# ADL5330.net
KiCad netlist of a schematic drawn in Altium Designer
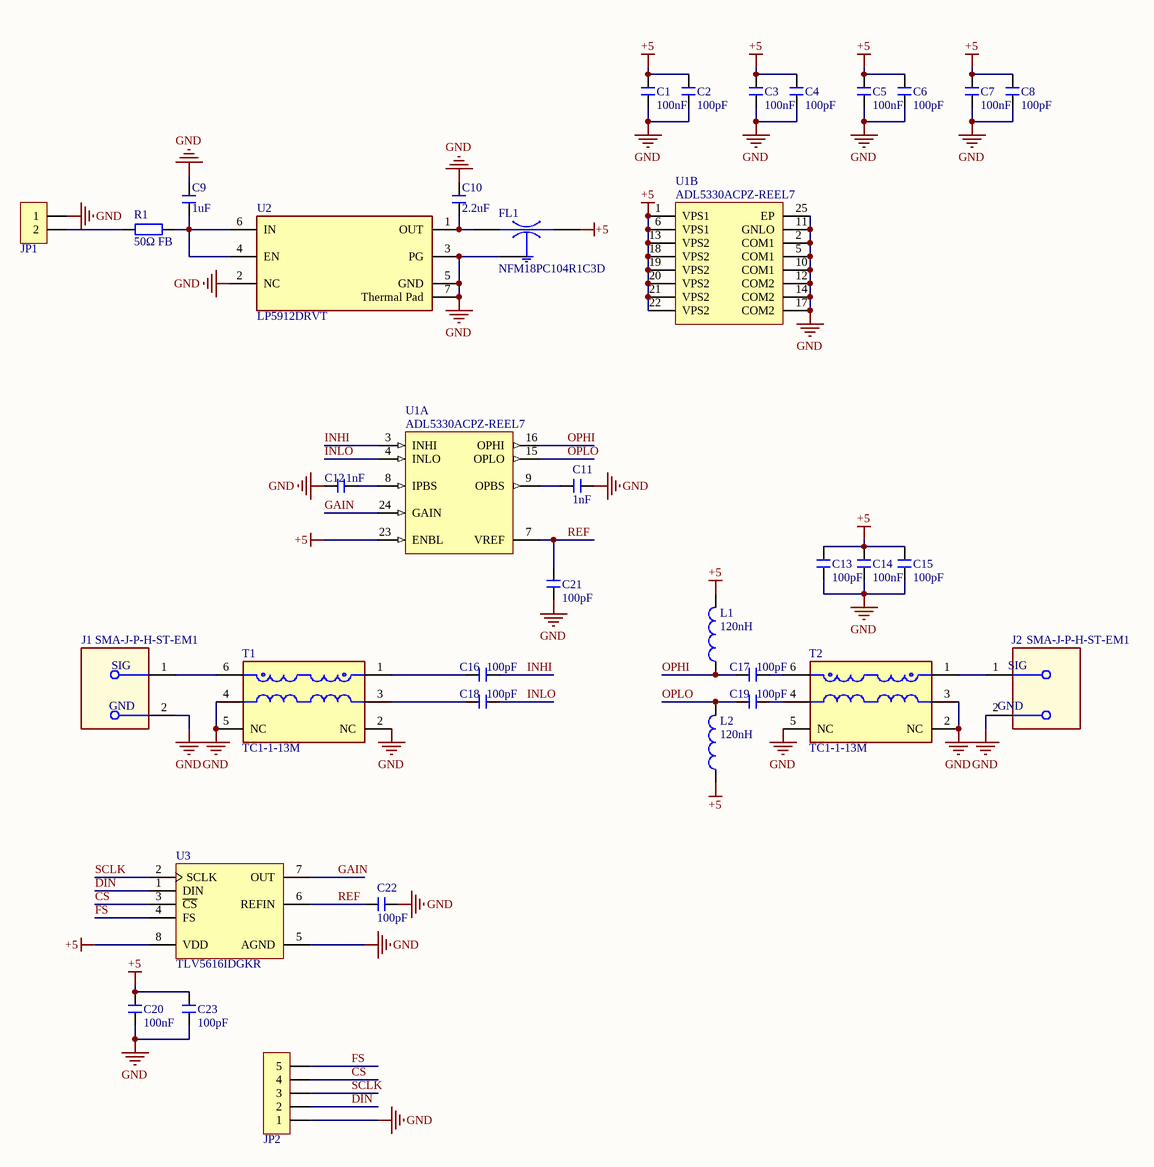
[diagram p0: ADL5330.SchDoc]

(export (version "E")
  (design (tool "Eeschema 10.0.6"))
  (components
    (comp (ref "C1")
      (value "100nF")
      (footprint "C 0402_L")
      (description "贴片电容")
      (libsource (lib "01 - 电容-电阻-电感") (part "C"))
    )
    (comp (ref "C2")
      (value "100pF")
      (footprint "C 0402_L")
      (description "贴片电容")
      (libsource (lib "01 - 电容-电阻-电感") (part "C"))
    )
    (comp (ref "C3")
      (value "100nF")
      (footprint "C 0402_L")
      (description "贴片电容")
      (libsource (lib "01 - 电容-电阻-电感") (part "C"))
    )
    (comp (ref "C4")
      (value "100pF")
      (footprint "C 0402_L")
      (description "贴片电容")
      (libsource (lib "01 - 电容-电阻-电感") (part "C"))
    )
    (comp (ref "C5")
      (value "100nF")
      (footprint "C 0402_L")
      (description "贴片电容")
      (libsource (lib "01 - 电容-电阻-电感") (part "C"))
    )
    (comp (ref "C6")
      (value "100pF")
      (footprint "C 0402_L")
      (description "贴片电容")
      (libsource (lib "01 - 电容-电阻-电感") (part "C"))
    )
    (comp (ref "C7")
      (value "100nF")
      (footprint "C 0402_L")
      (description "贴片电容")
      (libsource (lib "01 - 电容-电阻-电感") (part "C"))
    )
    (comp (ref "C8")
      (value "100pF")
      (footprint "C 0402_L")
      (description "贴片电容")
      (libsource (lib "01 - 电容-电阻-电感") (part "C"))
    )
    (comp (ref "C9")
      (value "1uF")
      (footprint "C 0603_L")
      (description "贴片电容")
      (libsource (lib "01 - 电容-电阻-电感") (part "C"))
    )
    (comp (ref "C10")
      (value "2.2uF")
      (footprint "C 0603_L")
      (description "贴片电容")
      (libsource (lib "01 - 电容-电阻-电感") (part "C"))
    )
    (comp (ref "C11")
      (value "1nF")
      (footprint "C 0402_L")
      (description "贴片电容")
      (libsource (lib "01 - 电容-电阻-电感") (part "C"))
    )
    (comp (ref "C12")
      (value "1nF")
      (footprint "C 0402_L")
      (description "贴片电容")
      (libsource (lib "01 - 电容-电阻-电感") (part "C"))
    )
    (comp (ref "C13")
      (value "100pF")
      (footprint "C 0402_L")
      (description "贴片电容")
      (libsource (lib "01 - 电容-电阻-电感") (part "C"))
    )
    (comp (ref "C14")
      (value "100nF")
      (footprint "C 0402_L")
      (description "贴片电容")
      (libsource (lib "01 - 电容-电阻-电感") (part "C"))
    )
    (comp (ref "C15")
      (value "100pF")
      (footprint "C 0402_L")
      (description "贴片电容")
      (libsource (lib "01 - 电容-电阻-电感") (part "C"))
    )
    (comp (ref "C16")
      (value "100pF")
      (footprint "C 0402_L")
      (description "贴片电容")
      (libsource (lib "01 - 电容-电阻-电感") (part "C"))
    )
    (comp (ref "C17")
      (value "100pF")
      (footprint "C 0402_L")
      (description "贴片电容")
      (libsource (lib "01 - 电容-电阻-电感") (part "C"))
    )
    (comp (ref "C18")
      (value "100pF")
      (footprint "C 0402_L")
      (description "贴片电容")
      (libsource (lib "01 - 电容-电阻-电感") (part "C"))
    )
    (comp (ref "C19")
      (value "100pF")
      (footprint "C 0402_L")
      (description "贴片电容")
      (libsource (lib "01 - 电容-电阻-电感") (part "C"))
    )
    (comp (ref "C20")
      (value "100nF")
      (footprint "C 0402_L")
      (description "贴片电容")
      (libsource (lib "01 - 电容-电阻-电感") (part "C"))
    )
    (comp (ref "C21")
      (value "100pF")
      (footprint "C 0402_L")
      (description "贴片电容")
      (libsource (lib "01 - 电容-电阻-电感") (part "C"))
    )
    (comp (ref "C22")
      (value "100pF")
      (footprint "C 0402_L")
      (description "贴片电容")
      (libsource (lib "01 - 电容-电阻-电感") (part "C"))
    )
    (comp (ref "C23")
      (value "100pF")
      (footprint "C 0402_L")
      (description "贴片电容")
      (libsource (lib "01 - 电容-电阻-电感") (part "C"))
    )
    (comp (ref "FL1")
      (value "NFM18PC104R1C3D")
      (footprint "FIL_NFM18PC104R1C3D")
      (description "SMD Capacitor with Capacitance: 0.10uF Tol. 20%. Rated Voltage: 16Vdc")
      (fields (field (name "MF") "Murata") (field (name "DIGI-KEY_PART_NUMBER") "490-6969-1-ND"))
      (libsource (lib "NFM18PC104R1C3D") (part "NFM18PC104R1C3D"))
    )
    (comp (ref "J1")
      (value "SMA-J-P-H-ST-EM1")
      (footprint "FP-SMA-J-P-H-ST-EM1-MFG")
      (description "CONN SMA JACK STR 50OHM EDGE MNT")
      (libsource (lib "") (part "CMP-02754-000006-1_1"))
    )
    (comp (ref "J2")
      (value "SMA-J-P-H-ST-EM1")
      (footprint "FP-SMA-J-P-H-ST-EM1-MFG")
      (description "CONN SMA JACK STR 50OHM EDGE MNT")
      (libsource (lib "卧式SMA") (part "CMP-02754-000006-1"))
    )
    (comp (ref "JP1")
      (value "HDR-1X2")
      (footprint "KF2510-LI-2P")
      (description "2P接插件")
      (libsource (lib "18 - 接插件-脚距2.54mm (100mil) ") (part "Header 2"))
    )
    (comp (ref "JP2")
      (value "HDR-1X5")
      (footprint "HDR2.54-LI-5P")
      (description "5P接插件")
      (libsource (lib "18 - 接插件-脚距2.54mm (100mil) ") (part "Header 5"))
    )
    (comp (ref "L1")
      (value "120nH")
      (footprint "L 0603")
      (description "小功率贴片电感")
      (libsource (lib "01 - 电容-电阻-电感") (part "L"))
    )
    (comp (ref "L2")
      (value "120nH")
      (footprint "L 0603")
      (description "小功率贴片电感")
      (libsource (lib "01 - 电容-电阻-电感") (part "L"))
    )
    (comp (ref "R1")
      (value "50Ω FB")
      (footprint "R 1206_L")
      (description "贴片电阻")
      (libsource (lib "01 - 电容-电阻-电感") (part "R"))
    )
    (comp (ref "T1")
      (value "TC1-1-13M")
      (footprint "FP-TC1-1-13M+-MFG")
      (description "RF Transformer 1: 1 5 Terminal SMD")
      (libsource (lib "TC1-1-13M+") (part "TC1-1-13M"))
    )
    (comp (ref "T2")
      (value "TC1-1-13M")
      (footprint "FP-TC1-1-13M+-MFG")
      (description "RF Transformer 1: 1 5 Terminal SMD")
      (libsource (lib "TC1-1-13M+") (part "TC1-1-13M"))
    )
    (comp (ref "U1")
      (value "ADL5330ACPZ-REEL7")
      (footprint "ADI-CP-24-2_L")
      (description "10 MHz to 3 GHz VGA with 60 dB Gain Control Range, 3GHz, CP-24-2, 1500 Reel, Pb-Free")
      (libsource (lib "ADL5330ACPZ") (part "ADL5330ACPZ"))
    )
    (comp (ref "U2")
      (value "LP5912DRVT")
      (footprint "FP-DRV0006A-MFG")
      (description "IC REG LINEAR 500MA 6SON")
      (libsource (lib "LP5912") (part "LP5912DRVT"))
    )
    (comp (ref "U3")
      (value "TLV5616IDGKR")
      (footprint "TI-DGK8_L")
      (fields (field (name "MANUFACTURER") "Texas Instruments"))
      (libsource (lib "TLV5616IDGKR") (part "CMP-0004-00436-1"))
    )
  )
  (nets
    (net (code "1") (name "+5") (class "Default")
      (node (ref "C1") (pin "2") (pinfunction "2_2") (pintype "passive"))
      (node (ref "C13") (pin "2") (pinfunction "2_2") (pintype "passive"))
      (node (ref "C14") (pin "2") (pinfunction "2_2") (pintype "passive"))
      (node (ref "C15") (pin "2") (pinfunction "2_2") (pintype "passive"))
      (node (ref "C2") (pin "2") (pinfunction "2_2") (pintype "passive"))
      (node (ref "C20") (pin "2") (pinfunction "2_2") (pintype "passive"))
      (node (ref "C23") (pin "1") (pinfunction "1_1") (pintype "passive"))
      (node (ref "C3") (pin "2") (pinfunction "2_2") (pintype "passive"))
      (node (ref "C4") (pin "2") (pinfunction "2_2") (pintype "passive"))
      (node (ref "C5") (pin "2") (pinfunction "2_2") (pintype "passive"))
      (node (ref "C6") (pin "2") (pinfunction "2_2") (pintype "passive"))
      (node (ref "C7") (pin "2") (pinfunction "2_2") (pintype "passive"))
      (node (ref "C8") (pin "2") (pinfunction "2_2") (pintype "passive"))
      (node (ref "FL1") (pin "3") (pinfunction "OUT_3") (pintype "passive"))
      (node (ref "L1") (pin "2") (pinfunction "2_2") (pintype "passive"))
      (node (ref "L2") (pin "1") (pinfunction "1_1") (pintype "passive"))
      (node (ref "U1") (pin "1") (pinfunction "VPS1_1") (pintype "power_in"))
      (node (ref "U1") (pin "13") (pinfunction "VPS2_13") (pintype "power_in"))
      (node (ref "U1") (pin "18") (pinfunction "VPS2_18") (pintype "power_in"))
      (node (ref "U1") (pin "19") (pinfunction "VPS2_19") (pintype "power_in"))
      (node (ref "U1") (pin "20") (pinfunction "VPS2_20") (pintype "power_in"))
      (node (ref "U1") (pin "21") (pinfunction "VPS2_21") (pintype "power_in"))
      (node (ref "U1") (pin "22") (pinfunction "VPS2_22") (pintype "power_in"))
      (node (ref "U1") (pin "23") (pinfunction "ENBL_23") (pintype "input"))
      (node (ref "U1") (pin "6") (pinfunction "VPS1_6") (pintype "power_in"))
      (node (ref "U3") (pin "8") (pinfunction "VDD_8") (pintype "power_in"))
    )
    (net (code "2") (name "/DIN") (class "Default")
      (node (ref "JP2") (pin "2") (pinfunction "2_2") (pintype "passive"))
      (node (ref "U3") (pin "1") (pinfunction "DIN_1") (pintype "passive"))
    )
    (net (code "3") (name "/FS") (class "Default")
      (node (ref "JP2") (pin "5") (pinfunction "5_5") (pintype "passive"))
      (node (ref "U3") (pin "4") (pinfunction "FS_4") (pintype "passive"))
    )
    (net (code "4") (name "/GAIN") (class "Default")
      (node (ref "U1") (pin "24") (pinfunction "GAIN_24") (pintype "input"))
      (node (ref "U3") (pin "7") (pinfunction "OUT_7") (pintype "passive"))
    )
    (net (code "5") (name "/INHI") (class "Default")
      (node (ref "C16") (pin "2") (pinfunction "2_2") (pintype "passive"))
      (node (ref "U1") (pin "3") (pinfunction "INHI_3") (pintype "input"))
    )
    (net (code "6") (name "/INLO") (class "Default")
      (node (ref "C18") (pin "2") (pinfunction "2_2") (pintype "passive"))
      (node (ref "U1") (pin "4") (pinfunction "INLO_4") (pintype "input"))
    )
    (net (code "7") (name "/OPHI") (class "Default")
      (node (ref "C17") (pin "1") (pinfunction "1_1") (pintype "passive"))
      (node (ref "L1") (pin "1") (pinfunction "1_1") (pintype "passive"))
      (node (ref "U1") (pin "16") (pinfunction "OPHI_16") (pintype "output"))
    )
    (net (code "8") (name "/OPLO") (class "Default")
      (node (ref "C19") (pin "1") (pinfunction "1_1") (pintype "passive"))
      (node (ref "L2") (pin "2") (pinfunction "2_2") (pintype "passive"))
      (node (ref "U1") (pin "15") (pinfunction "OPLO_15") (pintype "output"))
    )
    (net (code "9") (name "/REF") (class "Default")
      (node (ref "C21") (pin "2") (pinfunction "2_2") (pintype "passive"))
      (node (ref "C22") (pin "2") (pinfunction "2_2") (pintype "passive"))
      (node (ref "U1") (pin "7") (pinfunction "VREF_7") (pintype "passive"))
      (node (ref "U3") (pin "6") (pinfunction "REFIN_6") (pintype "passive"))
    )
    (net (code "10") (name "/SCLK") (class "Default")
      (node (ref "JP2") (pin "3") (pinfunction "3_3") (pintype "passive"))
      (node (ref "U3") (pin "2") (pinfunction "SCLK_2") (pintype "passive"))
    )
    (net (code "11") (name "/~{CS}") (class "Default")
      (node (ref "JP2") (pin "4") (pinfunction "4_4") (pintype "passive"))
      (node (ref "U3") (pin "3") (pinfunction "~{CS}_3") (pintype "passive"))
    )
    (net (code "12") (name "GND") (class "Default")
      (node (ref "C1") (pin "1") (pinfunction "1_1") (pintype "passive"))
      (node (ref "C10") (pin "2") (pinfunction "2_2") (pintype "passive"))
      (node (ref "C11") (pin "1") (pinfunction "1_1") (pintype "passive"))
      (node (ref "C12") (pin "1") (pinfunction "1_1") (pintype "passive"))
      (node (ref "C13") (pin "1") (pinfunction "1_1") (pintype "passive"))
      (node (ref "C14") (pin "1") (pinfunction "1_1") (pintype "passive"))
      (node (ref "C15") (pin "1") (pinfunction "1_1") (pintype "passive"))
      (node (ref "C2") (pin "1") (pinfunction "1_1") (pintype "passive"))
      (node (ref "C20") (pin "1") (pinfunction "1_1") (pintype "passive"))
      (node (ref "C21") (pin "1") (pinfunction "1_1") (pintype "passive"))
      (node (ref "C22") (pin "1") (pinfunction "1_1") (pintype "passive"))
      (node (ref "C23") (pin "2") (pinfunction "2_2") (pintype "passive"))
      (node (ref "C3") (pin "1") (pinfunction "1_1") (pintype "passive"))
      (node (ref "C4") (pin "1") (pinfunction "1_1") (pintype "passive"))
      (node (ref "C5") (pin "1") (pinfunction "1_1") (pintype "passive"))
      (node (ref "C6") (pin "1") (pinfunction "1_1") (pintype "passive"))
      (node (ref "C7") (pin "1") (pinfunction "1_1") (pintype "passive"))
      (node (ref "C8") (pin "1") (pinfunction "1_1") (pintype "passive"))
      (node (ref "C9") (pin "2") (pinfunction "2_2") (pintype "passive"))
      (node (ref "FL1") (pin "2") (pinfunction "GND_2") (pintype "power_in"))
      (node (ref "J1") (pin "2") (pinfunction "MNT_1_2") (pintype "passive"))
      (node (ref "J2") (pin "2") (pinfunction "MNT_1_2") (pintype "passive"))
      (node (ref "JP1") (pin "1") (pinfunction "1_1") (pintype "passive"))
      (node (ref "JP2") (pin "1") (pinfunction "1_1") (pintype "passive"))
      (node (ref "T1") (pin "2") (pinfunction "NC_2") (pintype "passive"))
      (node (ref "T1") (pin "4") (pinfunction "PRIMARY_4") (pintype "passive"))
      (node (ref "T1") (pin "5") (pinfunction "NC_5") (pintype "passive"))
      (node (ref "T2") (pin "2") (pinfunction "NC_2") (pintype "passive"))
      (node (ref "T2") (pin "3") (pinfunction "SECONDARY_3") (pintype "passive"))
      (node (ref "T2") (pin "5") (pinfunction "NC_5") (pintype "passive"))
      (node (ref "U1") (pin "10") (pinfunction "COM1_10") (pintype "power_in"))
      (node (ref "U1") (pin "11") (pinfunction "GNLO_11") (pintype "power_in"))
      (node (ref "U1") (pin "12") (pinfunction "COM2_12") (pintype "power_in"))
      (node (ref "U1") (pin "14") (pinfunction "COM2_14") (pintype "power_in"))
      (node (ref "U1") (pin "17") (pinfunction "COM2_17") (pintype "power_in"))
      (node (ref "U1") (pin "2") (pinfunction "COM1_2") (pintype "power_in"))
      (node (ref "U1") (pin "25") (pinfunction "EP_25") (pintype "power_in"))
      (node (ref "U1") (pin "5") (pinfunction "COM1_5") (pintype "power_in"))
      (node (ref "U2") (pin "2") (pinfunction "NC_2") (pintype "passive"))
      (node (ref "U2") (pin "3") (pinfunction "PG_3") (pintype "passive"))
      (node (ref "U2") (pin "5") (pinfunction "GND_5") (pintype "power_in"))
      (node (ref "U2") (pin "7") (pinfunction "Thermal_Pad_7") (pintype "power_in"))
      (node (ref "U3") (pin "5") (pinfunction "AGND_5") (pintype "power_in"))
    )
    (net (code "13") (name "Net-(FL1-IN)") (class "Default")
      (node (ref "C10") (pin "1") (pinfunction "1_1") (pintype "passive"))
      (node (ref "FL1") (pin "1") (pinfunction "IN_1") (pintype "passive"))
      (node (ref "U2") (pin "1") (pinfunction "OUT_1") (pintype "power_in"))
    )
    (net (code "14") (name "Net-(JP1-Pad2)") (class "Default")
      (node (ref "JP1") (pin "2") (pinfunction "2_2") (pintype "passive"))
      (node (ref "R1") (pin "1") (pinfunction "1_1") (pintype "passive"))
    )
    (net (code "15") (name "Net-(T1-PRIMARY_DOT)") (class "Default")
      (node (ref "J1") (pin "1") (pinfunction "1_1") (pintype "passive"))
      (node (ref "T1") (pin "6") (pinfunction "PRIMARY_DOT_6") (pintype "passive"))
    )
    (net (code "16") (name "Net-(T1-SECONDARY)") (class "Default")
      (node (ref "C18") (pin "1") (pinfunction "1_1") (pintype "passive"))
      (node (ref "T1") (pin "3") (pinfunction "SECONDARY_3") (pintype "passive"))
    )
    (net (code "17") (name "Net-(T1-SECONDARY_DOT)") (class "Default")
      (node (ref "C16") (pin "1") (pinfunction "1_1") (pintype "passive"))
      (node (ref "T1") (pin "1") (pinfunction "SECONDARY_DOT_1") (pintype "passive"))
    )
    (net (code "18") (name "Net-(T2-PRIMARY)") (class "Default")
      (node (ref "C19") (pin "2") (pinfunction "2_2") (pintype "passive"))
      (node (ref "T2") (pin "4") (pinfunction "PRIMARY_4") (pintype "passive"))
    )
    (net (code "19") (name "Net-(T2-PRIMARY_DOT)") (class "Default")
      (node (ref "C17") (pin "2") (pinfunction "2_2") (pintype "passive"))
      (node (ref "T2") (pin "6") (pinfunction "PRIMARY_DOT_6") (pintype "passive"))
    )
    (net (code "20") (name "Net-(T2-SECONDARY_DOT)") (class "Default")
      (node (ref "J2") (pin "1") (pinfunction "1_1") (pintype "passive"))
      (node (ref "T2") (pin "1") (pinfunction "SECONDARY_DOT_1") (pintype "passive"))
    )
    (net (code "21") (name "Net-(U1A-IPBS)") (class "Default")
      (node (ref "C12") (pin "2") (pinfunction "2_2") (pintype "passive"))
      (node (ref "U1") (pin "8") (pinfunction "IPBS_8") (pintype "input"))
    )
    (net (code "22") (name "Net-(U1A-OPBS)") (class "Default")
      (node (ref "C11") (pin "2") (pinfunction "2_2") (pintype "passive"))
      (node (ref "U1") (pin "9") (pinfunction "OPBS_9") (pintype "output"))
    )
    (net (code "23") (name "Net-(U2-EN)") (class "Default")
      (node (ref "C9") (pin "1") (pinfunction "1_1") (pintype "passive"))
      (node (ref "R1") (pin "2") (pinfunction "2_2") (pintype "passive"))
      (node (ref "U2") (pin "4") (pinfunction "EN_4") (pintype "passive"))
      (node (ref "U2") (pin "6") (pinfunction "IN_6") (pintype "power_in"))
    )
  )
)
